# EFR32xG22_ESL-Node_Ref-Des_Sheet2.net
KiCad netlist of a schematic drawn in Altium Designer
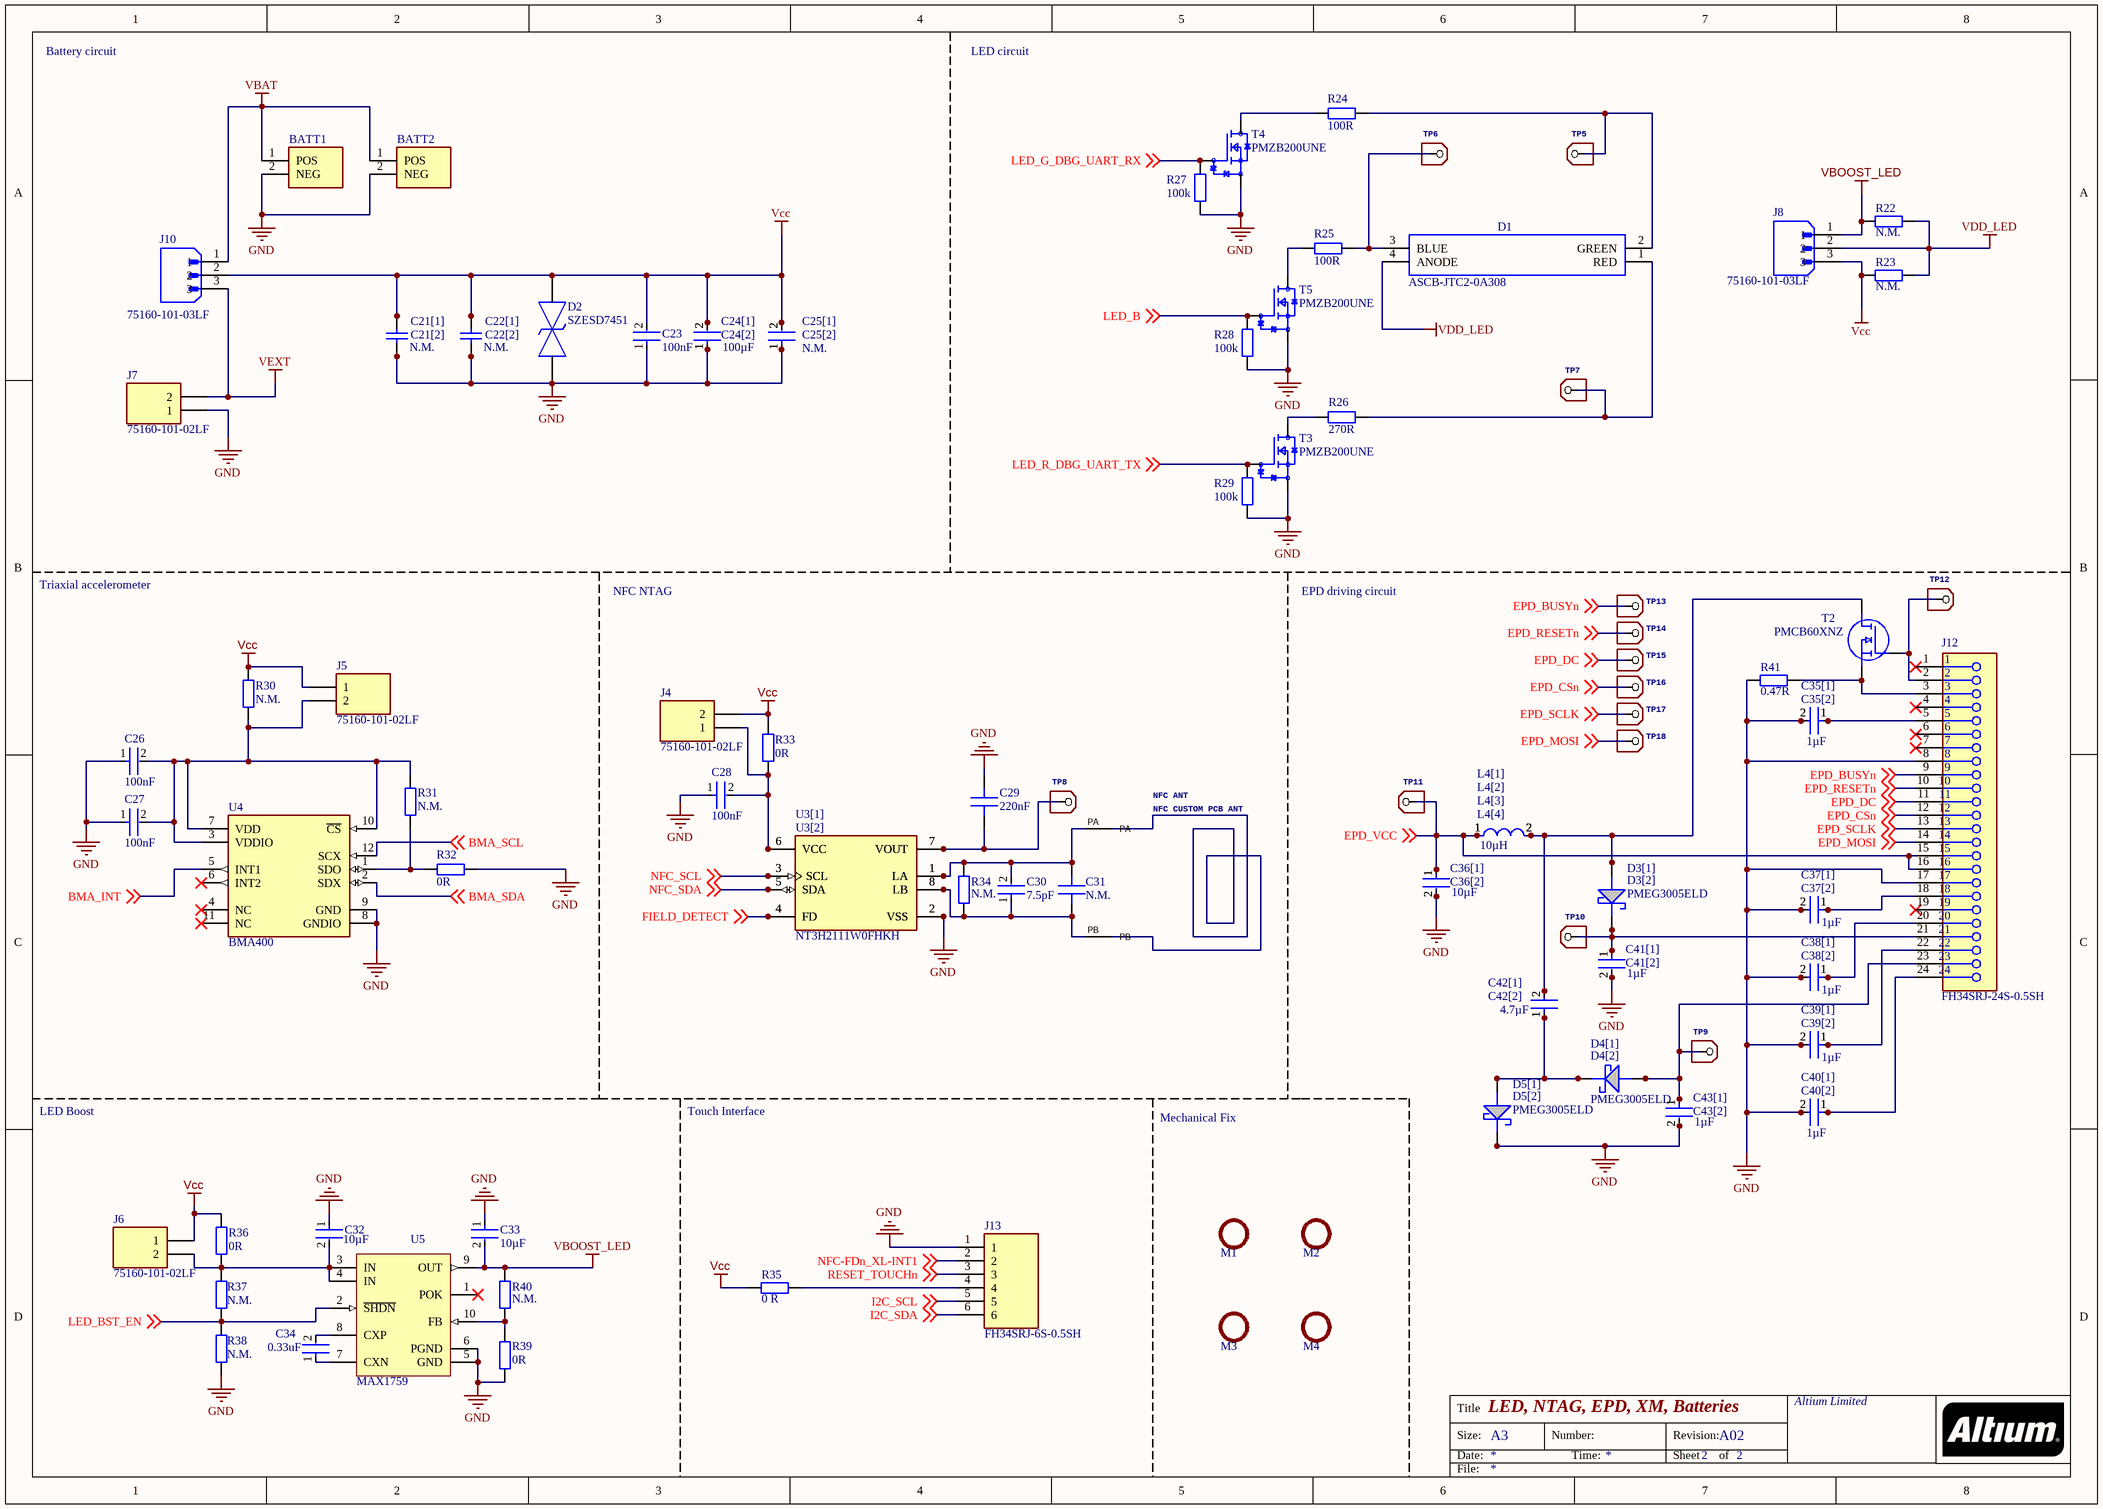
[diagram p0: EFR32xG22_ESL-Node_Ref-Des_Sheet2.SchDoc]

(export (version "E")
  (design (tool "Eeschema 10.0.6"))
  (components
    (comp (ref "BATT1")
      (value "1052TR")
      (footprint "Battery_holder_CR2450_SMT_1052")
      (description "Battery Holder _Open_ Coin, 24.5mm 1 Cell SMD _SMT_ Tab")
      (fields (field (name "MF") "Keystone Electronics"))
      (libsource (lib "EFR32xG22_ESL-Node_Ref-Des_1") (part "1052TR"))
    )
    (comp (ref "BATT2")
      (value "1052TR")
      (footprint "Battery_holder_CR2450_SMT_1052")
      (description "Battery Holder _Open_ Coin, 24.5mm 1 Cell SMD _SMT_ Tab")
      (fields (field (name "MF") "Keystone Electronics"))
      (libsource (lib "EFR32xG22_ESL-Node_Ref-Des_1") (part "1052TR"))
    )
    (comp (ref "C21[1]")
      (value "N.M.")
      (footprint "1206")
      (description "Chip Capacitor, 100 uF, +/- 20%, 6.3 V, -55 to 85 degC, 1206 (3216 Metric), RoHS, Tape and Reel")
      (fields (field (name "TOLERANCE") "20%") (field (name "PARTNUMBER") "GRM31CR60J107ME39L"))
      (libsource (lib "altium-import") (part "root_1_CAP-NP-2_"))
    )
    (comp (ref "C21[2]")
      (value "N.M.")
      (footprint "0805")
      (description "Chip Capacitor, 100 uF, +/- 20%, 6.3 V, -55 to 85 degC, 1206 (3216 Metric), RoHS, Tape and Reel")
      (fields (field (name "TOLERANCE") "20%") (field (name "PARTNUMBER") "GRM31CR60J107ME39L"))
      (libsource (lib "altium-import") (part "root_1_CAP-NP-2_"))
    )
    (comp (ref "C22[1]")
      (value "N.M.")
      (footprint "1206")
      (description "Chip Capacitor, 100 uF, +/- 20%, 6.3 V, -55 to 85 degC, 1206 (3216 Metric), RoHS, Tape and Reel")
      (fields (field (name "TOLERANCE") "20%") (field (name "PARTNUMBER") "GRM31CR60J107ME39L"))
      (libsource (lib "altium-import") (part "root_1_CAP-NP-2_"))
    )
    (comp (ref "C22[2]")
      (value "N.M.")
      (footprint "0805")
      (description "Chip Capacitor, 100 uF, +/- 20%, 6.3 V, -55 to 85 degC, 1206 (3216 Metric), RoHS, Tape and Reel")
      (fields (field (name "TOLERANCE") "20%") (field (name "PARTNUMBER") "GRM31CR60J107ME39L"))
      (libsource (lib "altium-import") (part "root_1_CAP-NP-2_"))
    )
    (comp (ref "C23")
      (value "100nF")
      (footprint "0402")
      (description "Ceramic Capacitor for Automotive 100nF ±10% 16VDC X7R 0402 Paper T/R")
      (fields (field (name "TOLERANCE") "10%"))
      (libsource (lib "altium-import") (part "root_2_02cd4be3c70576c341d710602a673aa_"))
    )
    (comp (ref "C24[1]")
      (value "100µF")
      (footprint "1206")
      (description "CAP CER 100UF 6.3V X5R 1206")
      (fields (field (name "VOLTAGE") "6.3V") (field (name "TOLERANCE") "20%"))
      (libsource (lib "altium-import") (part "root_2_b4654b650e69147ec39a6b967a45e02_"))
    )
    (comp (ref "C24[2]")
      (value "100µF")
      (footprint "0805")
      (description "CAP CER 100UF 6.3V X5R 1206")
      (fields (field (name "VOLTAGE") "6.3V") (field (name "TOLERANCE") "20%"))
      (libsource (lib "altium-import") (part "root_2_b4654b650e69147ec39a6b967a45e02_"))
    )
    (comp (ref "C25[1]")
      (value "N.M.")
      (footprint "1206")
      (description "CAP CER 100UF 6.3V X5R 1206")
      (fields (field (name "VOLTAGE") "6.3V") (field (name "TOLERANCE") "20%"))
      (libsource (lib "altium-import") (part "root_2_b4654b650e69147ec39a6b967a45e02_"))
    )
    (comp (ref "C25[2]")
      (value "100µF")
      (footprint "0805")
      (description "CAP CER 100UF 6.3V X5R 1206")
      (fields (field (name "VOLTAGE") "6.3V") (field (name "TOLERANCE") "20%"))
      (libsource (lib "altium-import") (part "root_2_b4654b650e69147ec39a6b967a45e02_"))
    )
    (comp (ref "C26")
      (value "100nF")
      (footprint "0402")
      (description "Ceramic Capacitor for Automotive 100nF ±10% 16VDC X7R 0402 Paper T/R")
      (fields (field (name "TOLERANCE") "10%"))
      (libsource (lib "altium-import") (part "root_1_02cd4be3c70576c341d710602a673aa_"))
    )
    (comp (ref "C27")
      (value "100nF")
      (footprint "0402")
      (description "Ceramic Capacitor for Automotive 100nF ±10% 16VDC X7R 0402 Paper T/R")
      (fields (field (name "TOLERANCE") "10%"))
      (libsource (lib "altium-import") (part "root_1_02cd4be3c70576c341d710602a673aa_"))
    )
    (comp (ref "C28")
      (value "100nF")
      (footprint "0201")
      (description "Chip Multilayer Ceramic Capacitors for General Purpose, 0201, 0.10uF, X5R, 15%, 10%, 10V")
      (fields (field (name "TOLERANCE") "10%") (field (name "VOLTAGE") "10V"))
      (libsource (lib "altium-import") (part "root_1_b4654b650e69147ec39a6b967a45e02_"))
    )
    (comp (ref "C29")
      (value "220nF")
      (footprint "0201")
      (description "CAP CER 1000PF 10V X7R 0201 10%")
      (fields (field (name "TOLERANCE") "10%"))
      (libsource (lib "altium-import") (part "root_3_Capacitor_"))
    )
    (comp (ref "C30")
      (value "7.5pF")
      (footprint "0201")
      (description "Chip Multilayer Ceramic Capacitors for General Purpose, 0201, 7.5pF, C0G, 30ppm/°C, 0.1pF, 50V")
      (libsource (lib "altium-import") (part "root_2_b4654b650e69147ec39a6b967a45e02_"))
    )
    (comp (ref "C31")
      (value "N.M.")
      (footprint "0201")
      (description "CAP CER 0201 C0G 1.2pF 50V 0.05pF")
      (fields (field (name "TOLERANCE") "0.05pF"))
      (libsource (lib "altium-import") (part "root_1_Capacitor_"))
    )
    (comp (ref "C32")
      (value "10µF")
      (footprint "0603")
      (description "Chip Multilayer Ceramic Capacitors for General Purpose, 0603, 10uF, X5R, 15%, 20%, 25V")
      (fields (field (name "TOLERANCE") "20%") (field (name "VOLTAGE") "25V"))
      (libsource (lib "altium-import") (part "root_0_11868f565c42a9108669ba33697ecf6_"))
    )
    (comp (ref "C33")
      (value "10µF")
      (footprint "0603")
      (description "Chip Multilayer Ceramic Capacitors for General Purpose, 0603, 10uF, X5R, 15%, 20%, 25V")
      (fields (field (name "TOLERANCE") "20%") (field (name "VOLTAGE") "25V"))
      (libsource (lib "altium-import") (part "root_0_11868f565c42a9108669ba33697ecf6_"))
    )
    (comp (ref "C34")
      (value "0.33uF")
      (footprint "0603")
      (description "Ceramic Capacitor for Automotive 330nF  ±10% 16VDC X7R 0603 Paper T/R")
      (fields (field (name "TOLERANCE") "10%"))
      (libsource (lib "altium-import") (part "root_2_02cd4be3c70576c341d710602a673aa_"))
    )
    (comp (ref "C35[1]")
      (value "1µF")
      (footprint "0603")
      (description "Ceramic Capacitor for Automotive 1uF  ±10% 25VDC X7R 0603 Paper T/R")
      (fields (field (name "TOLERANCE") "10%") (field (name "VOLTAGE") "25V"))
      (libsource (lib "altium-import") (part "root_3_02cd4be3c70576c341d710602a673aa_"))
    )
    (comp (ref "C35[2]")
      (value "1µF")
      (footprint "0402")
      (description "Ceramic Capacitor for Automotive 1uF  ±10% 25VDC X7R 0603 Paper T/R")
      (fields (field (name "TOLERANCE") "10%") (field (name "VOLTAGE") "25V"))
      (libsource (lib "altium-import") (part "root_3_02cd4be3c70576c341d710602a673aa_"))
    )
    (comp (ref "C36[1]")
      (value "10µF")
      (footprint "0603")
      (description "CAP CER 10UF 10V X5R 0603")
      (fields
        (field (name "OCTOPART") "https://octopart.com/grm188r61a106ke69d-murata-22851381")
        (field (name "MANUFACTURER PART NUMBER") "GRM188R61A106KE69D")
      )
      (libsource (lib "altium-import") (part "root_0_11868f565c42a9108669ba33697ecf6_"))
    )
    (comp (ref "C36[2]")
      (value "10µF")
      (footprint "0402")
      (description "CAP CER 10UF 10V X5R 0603")
      (fields
        (field (name "OCTOPART") "https://octopart.com/grm188r61a106ke69d-murata-22851381")
        (field (name "MANUFACTURER PART NUMBER") "GRM188R61A106KE69D")
      )
      (libsource (lib "altium-import") (part "root_0_11868f565c42a9108669ba33697ecf6_"))
    )
    (comp (ref "C37[1]")
      (value "1µF")
      (footprint "0603")
      (description "Ceramic Capacitor for Automotive 1uF  ±10% 25VDC X7R 0603 Paper T/R")
      (fields (field (name "TOLERANCE") "10%") (field (name "VOLTAGE") "25V"))
      (libsource (lib "altium-import") (part "root_3_02cd4be3c70576c341d710602a673aa_"))
    )
    (comp (ref "C37[2]")
      (value "1µF")
      (footprint "0402")
      (description "Ceramic Capacitor for Automotive 1uF  ±10% 25VDC X7R 0603 Paper T/R")
      (fields (field (name "TOLERANCE") "10%") (field (name "VOLTAGE") "25V"))
      (libsource (lib "altium-import") (part "root_3_02cd4be3c70576c341d710602a673aa_"))
    )
    (comp (ref "C38[1]")
      (value "1µF")
      (footprint "0603")
      (description "Ceramic Capacitor for Automotive 1uF  ±10% 25VDC X7R 0603 Paper T/R")
      (fields (field (name "TOLERANCE") "10%") (field (name "VOLTAGE") "25V"))
      (libsource (lib "altium-import") (part "root_3_02cd4be3c70576c341d710602a673aa_"))
    )
    (comp (ref "C38[2]")
      (value "1µF")
      (footprint "0402")
      (description "Ceramic Capacitor for Automotive 1uF  ±10% 25VDC X7R 0603 Paper T/R")
      (fields (field (name "TOLERANCE") "10%") (field (name "VOLTAGE") "25V"))
      (libsource (lib "altium-import") (part "root_3_02cd4be3c70576c341d710602a673aa_"))
    )
    (comp (ref "C39[1]")
      (value "1µF")
      (footprint "0603")
      (description "Ceramic Capacitor for Automotive 1uF  ±10% 25VDC X7R 0603 Paper T/R")
      (fields (field (name "TOLERANCE") "10%") (field (name "VOLTAGE") "25V"))
      (libsource (lib "altium-import") (part "root_3_02cd4be3c70576c341d710602a673aa_"))
    )
    (comp (ref "C39[2]")
      (value "1µF")
      (footprint "0402")
      (description "Ceramic Capacitor for Automotive 1uF  ±10% 25VDC X7R 0603 Paper T/R")
      (fields (field (name "TOLERANCE") "10%") (field (name "VOLTAGE") "25V"))
      (libsource (lib "altium-import") (part "root_3_02cd4be3c70576c341d710602a673aa_"))
    )
    (comp (ref "C40[1]")
      (value "1µF")
      (footprint "0603")
      (description "Ceramic Capacitor for Automotive 1uF  ±10% 25VDC X7R 0603 Paper T/R")
      (fields (field (name "TOLERANCE") "10%") (field (name "VOLTAGE") "25V"))
      (libsource (lib "altium-import") (part "root_3_02cd4be3c70576c341d710602a673aa_"))
    )
    (comp (ref "C40[2]")
      (value "1µF")
      (footprint "0402")
      (description "Ceramic Capacitor for Automotive 1uF  ±10% 25VDC X7R 0603 Paper T/R")
      (fields (field (name "TOLERANCE") "10%") (field (name "VOLTAGE") "25V"))
      (libsource (lib "altium-import") (part "root_3_02cd4be3c70576c341d710602a673aa_"))
    )
    (comp (ref "C41[1]")
      (value "1µF")
      (footprint "0603")
      (description "CAP CER 10UF 10V X5R 0603")
      (fields
        (field (name "OCTOPART") "https://octopart.com/grm188r61a106ke69d-murata-22851381")
        (field (name "MANUFACTURER PART NUMBER") "GRM188R61A106KE69D")
      )
      (libsource (lib "altium-import") (part "root_0_11868f565c42a9108669ba33697ecf6_"))
    )
    (comp (ref "C41[2]")
      (value "1µF")
      (footprint "0402")
      (description "CAP CER 10UF 10V X5R 0603")
      (fields
        (field (name "OCTOPART") "https://octopart.com/grm188r61a106ke69d-murata-22851381")
        (field (name "MANUFACTURER PART NUMBER") "GRM188R61A106KE69D")
      )
      (libsource (lib "altium-import") (part "root_0_11868f565c42a9108669ba33697ecf6_"))
    )
    (comp (ref "C42[1]")
      (value "4.7µF")
      (footprint "0603")
      (description "CAP CER 10UF 10V X5R 0603")
      (fields
        (field (name "OCTOPART") "https://octopart.com/grm188r61a106ke69d-murata-22851381")
        (field (name "MANUFACTURER PART NUMBER") "GRM188R61A106KE69D")
      )
      (libsource (lib "altium-import") (part "root_2_11868f565c42a9108669ba33697ecf6_"))
    )
    (comp (ref "C42[2]")
      (value "4.7µF")
      (footprint "0402")
      (description "CAP CER 10UF 10V X5R 0603")
      (fields
        (field (name "OCTOPART") "https://octopart.com/grm188r61a106ke69d-murata-22851381")
        (field (name "MANUFACTURER PART NUMBER") "GRM188R61A106KE69D")
      )
      (libsource (lib "altium-import") (part "root_2_11868f565c42a9108669ba33697ecf6_"))
    )
    (comp (ref "C43[1]")
      (value "1µF")
      (footprint "0603")
      (description "CAP CER 10UF 10V X5R 0603")
      (fields
        (field (name "OCTOPART") "https://octopart.com/grm188r61a106ke69d-murata-22851381")
        (field (name "MANUFACTURER PART NUMBER") "GRM188R61A106KE69D")
      )
      (libsource (lib "altium-import") (part "root_0_11868f565c42a9108669ba33697ecf6_"))
    )
    (comp (ref "C43[2]")
      (value "1µF")
      (footprint "0402")
      (description "CAP CER 10UF 10V X5R 0603")
      (fields
        (field (name "OCTOPART") "https://octopart.com/grm188r61a106ke69d-murata-22851381")
        (field (name "MANUFACTURER PART NUMBER") "GRM188R61A106KE69D")
      )
      (libsource (lib "altium-import") (part "root_0_11868f565c42a9108669ba33697ecf6_"))
    )
    (comp (ref "D1")
      (value "ASCB-JTC2-0A308")
      (footprint "LED_RGB_PLCC-4")
      (description "Standard LEDs - SMD 1615 Tricolor PLCC-4 LED")
      (fields (field (name "MOUSER PART NUMBER") "630-ASCB-JTC2-0A308"))
      (libsource (lib "ASCBJTC20A308") (part "ASCB-JTC2-0A308"))
    )
    (comp (ref "D2")
      (value "SZESD7451")
      (footprint "SOD882_NXP")
      (description "ESD Suppressors / TVS Diodes BI-DIRECTIONAL 5V ESD PR")
      (fields
        (field (name "MANUFACTURER_PART_NUMBER") "ESD7551N2T5G")
        (field (name "MOUSER PART NUMBER") "863-ESD7551N2T5G")
      )
      (libsource (lib "EFR32xG22_ESL-Node_Ref-Des_1") (part "ESD7551N2T5G"))
    )
    (comp (ref "D3[1]")
      (value "PMEG3005ELD")
      (footprint "SOD-323")
      (description "Schottky Diodes & Rectifiers Schottky Diode")
      (fields
        (field (name "MANUFACTURER_PART_NUMBER") "PMEG3005ELD,315")
        (field (name "MOUSER PART NUMBER") "771-PMEG3005ELD315")
      )
      (libsource (lib "EFR32xG22_ESL-Node_Ref-Des_1") (part "PMEG3005ELD_315"))
    )
    (comp (ref "D3[2]")
      (value "PMEG3005ELD")
      (footprint "SOD882_FIXED")
      (description "Schottky Diodes & Rectifiers Schottky Diode")
      (fields
        (field (name "MANUFACTURER_PART_NUMBER") "PMEG3005ELD,315")
        (field (name "MOUSER PART NUMBER") "771-PMEG3005ELD315")
      )
      (libsource (lib "EFR32xG22_ESL-Node_Ref-Des_1") (part "PMEG3005ELD_315"))
    )
    (comp (ref "D4[1]")
      (value "PMEG3005ELD")
      (footprint "SOD-323")
      (description "Schottky Diodes & Rectifiers Schottky Diode")
      (fields
        (field (name "MANUFACTURER_PART_NUMBER") "PMEG3005ELD,315")
        (field (name "MOUSER PART NUMBER") "771-PMEG3005ELD315")
      )
      (libsource (lib "EFR32xG22_ESL-Node_Ref-Des_1") (part "PMEG3005ELD_315"))
    )
    (comp (ref "D4[2]")
      (value "PMEG3005ELD")
      (footprint "SOD882_FIXED")
      (description "Schottky Diodes & Rectifiers Schottky Diode")
      (fields
        (field (name "MANUFACTURER_PART_NUMBER") "PMEG3005ELD,315")
        (field (name "MOUSER PART NUMBER") "771-PMEG3005ELD315")
      )
      (libsource (lib "EFR32xG22_ESL-Node_Ref-Des_1") (part "PMEG3005ELD_315"))
    )
    (comp (ref "D5[1]")
      (value "PMEG3005ELD")
      (footprint "SOD-323")
      (description "Schottky Diodes & Rectifiers Schottky Diode")
      (fields
        (field (name "MANUFACTURER_PART_NUMBER") "PMEG3005ELD,315")
        (field (name "MOUSER PART NUMBER") "771-PMEG3005ELD315")
      )
      (libsource (lib "EFR32xG22_ESL-Node_Ref-Des_1") (part "PMEG3005ELD_315"))
    )
    (comp (ref "D5[2]")
      (value "PMEG3005ELD")
      (footprint "SOD882_FIXED")
      (description "Schottky Diodes & Rectifiers Schottky Diode")
      (fields
        (field (name "MANUFACTURER_PART_NUMBER") "PMEG3005ELD,315")
        (field (name "MOUSER PART NUMBER") "771-PMEG3005ELD315")
      )
      (libsource (lib "EFR32xG22_ESL-Node_Ref-Des_1") (part "PMEG3005ELD_315"))
    )
    (comp (ref "J4")
      (value "75160-101-02LF")
      (footprint "Jumper_HDR_2.54mm")
      (fields (field (name "MP") "HTSW10228FS") (field (name "MF") "Samtec"))
      (libsource (lib "EFR32xG22_ESL-Node_Ref-Des_1") (part "HTSW-102-28-F-S"))
    )
    (comp (ref "J5")
      (value "75160-101-02LF")
      (footprint "Jumper_HDR_2.54mm")
      (fields (field (name "MP") "HTSW10228FS") (field (name "MF") "Samtec"))
      (libsource (lib "") (part "HTSW-102-28-F-S_2"))
    )
    (comp (ref "J6")
      (value "75160-101-02LF")
      (footprint "Jumper_HDR_2.54mm")
      (fields (field (name "MP") "HTSW10228FS") (field (name "MF") "Samtec"))
      (libsource (lib "") (part "HTSW-102-28-F-S_1"))
    )
    (comp (ref "J7")
      (value "75160-101-02LF")
      (footprint "Jumper_HDR_2.54mm")
      (fields (field (name "MP") "HTSW10228FS") (field (name "MF") "Samtec"))
      (libsource (lib "EFR32xG22_ESL-Node_Ref-Des_1") (part "HTSW-102-28-F-S"))
    )
    (comp (ref "J8")
      (value "75160-101-03LF")
      (footprint "Jumper_HDR_2.54mm_3p")
      (fields (field (name "MF") "Amphenol ICC (FCI)"))
      (libsource (lib "75160-101-03LF") (part "75160-101-03LF"))
    )
    (comp (ref "J10")
      (value "75160-101-03LF")
      (footprint "Jumper_HDR_2.54mm_3p")
      (fields (field (name "MF") "Amphenol ICC (FCI)"))
      (libsource (lib "75160-101-03LF") (part "75160-101-03LF"))
    )
    (comp (ref "J12")
      (value "FH34SRJ-24S-0.5SH")
      (footprint "FPC_CONNECTOR_24_0.5MM_PITCH_BOTTOM_CONTACT_ACES_1.3MM_50530")
      (description "CONN FPC/FFC 24POS .5MM")
      (libsource (lib "EFR32xG22_ESL-Node_Ref-Des_1") (part "CMP-11609-000022-1"))
    )
    (comp (ref "J13")
      (value "FH34SRJ-6S-0.5SH")
      (footprint "FH34SRJ-6S-0.5SH")
      (fields (field (name "MP") "FH34SRJ-6S-0.5SH(50)"))
      (libsource (lib "EFR32xG22_ESL-Node_Ref-Des_1") (part "FH34SRJ-6S-0.5SH(50)"))
    )
    (comp (ref "L4[1]")
      (value "10µH")
      (footprint "0805")
      (description "SMD Inductors 10uH ±10% 0.52A 0.65Ω 0806")
      (fields (field (name "TOLERANCE") "10%"))
      (libsource (lib "altium-import") (part "root_0_725321dda6339637d4d059423bc1c3c_"))
    )
    (comp (ref "L4[2]")
      (value "10µH")
      (footprint "0806")
      (description "SMD Inductors 10uH ±10% 0.52A 0.65Ω 0806")
      (fields (field (name "TOLERANCE") "10%"))
      (libsource (lib "altium-import") (part "root_0_725321dda6339637d4d059423bc1c3c_"))
    )
    (comp (ref "L4[3]")
      (value "10µH")
      (footprint "2520")
      (description "SMD Inductors 10uH ±10% 0.52A 0.65Ω 0806")
      (fields (field (name "TOLERANCE") "10%"))
      (libsource (lib "altium-import") (part "root_0_725321dda6339637d4d059423bc1c3c_"))
    )
    (comp (ref "L4[4]")
      (value "10µH")
      (footprint "WE-MAPI-3015")
      (description "SMD Inductors 10uH ±10% 0.52A 0.65Ω 0806")
      (fields (field (name "TOLERANCE") "10%"))
      (libsource (lib "altium-import") (part "root_0_725321dda6339637d4d059423bc1c3c_"))
    )
    (comp (ref "M1")
      (value "HOLE_2.2_NPL")
      (footprint "HOLE_2.2_NPL")
      (libsource (lib "EFR32xG22_ESL-Node_Ref-Des_Sheet2") (part "HOLE_2.2_NPL"))
    )
    (comp (ref "M2")
      (value "HOLE_2.2_NPL")
      (footprint "HOLE_2.2_NPL")
      (libsource (lib "EFR32xG22_ESL-Node_Ref-Des_Sheet2") (part "HOLE_2.2_NPL"))
    )
    (comp (ref "M3")
      (value "HOLE_2.2_NPL")
      (footprint "HOLE_2.2_NPL")
      (libsource (lib "EFR32xG22_ESL-Node_Ref-Des_Sheet2") (part "HOLE_2.2_NPL"))
    )
    (comp (ref "M4")
      (value "HOLE_2.2_NPL")
      (footprint "HOLE_2.2_NPL")
      (libsource (lib "EFR32xG22_ESL-Node_Ref-Des_Sheet2") (part "HOLE_2.2_NPL"))
    )
    (comp (ref "NFC ANT")
      (value "NFC CUSTOM PCB ANT")
      (footprint "NFC_27X14.3_7W_WIDTH0.25MM_SPACE0.2MM_1.5UH_V1_0_NOVIASTOP")
      (description "Custom NFC Printed Antenna")
      (libsource (lib "EFR32xG22_ESL-Node_Ref-Des_1") (part "NFC_ANTENNA_custom"))
    )
    (comp (ref "R22")
      (value "N.M.")
      (footprint "0603")
      (fields (field (name "MANUFACTURER") "Vishay Dale") (field (name "PART NUMBER") "CRCW06030000Z0EC"))
      (libsource (lib "altium-import") (part "root_2_RES_"))
    )
    (comp (ref "R23")
      (value "N.M.")
      (footprint "0603")
      (fields (field (name "MANUFACTURER") "Vishay Dale") (field (name "PART NUMBER") "CRCW06030000Z0EC"))
      (libsource (lib "altium-import") (part "root_2_RES_"))
    )
    (comp (ref "R24")
      (value "100R")
      (footprint "0201")
      (description "RES 0201 100R 1/20W 1% 200ppm")
      (fields (field (name "TOLERANCE") "1%"))
      (libsource (lib "altium-import") (part "root_0_Resistor_"))
    )
    (comp (ref "R25")
      (value "100R")
      (footprint "0201")
      (description "RES 0201 100R 1/20W 1% 200ppm")
      (fields (field (name "TOLERANCE") "1%"))
      (libsource (lib "altium-import") (part "root_0_Resistor_"))
    )
    (comp (ref "R26")
      (value "270R")
      (footprint "0201")
      (description "240R 0.05W 5% 0201 (0603 Metric)  SMD")
      (fields (field (name "TOLERANCE") "5 %") (field (name "POWER") "0.05 W"))
      (libsource (lib "altium-import") (part "root_0_RES_"))
    )
    (comp (ref "R27")
      (value "100k")
      (footprint "0201")
      (description "100K 0.05W 1% 0201 (0603 Metric)  SMD")
      (fields (field (name "POWER") "0.05 W") (field (name "TOLERANCE") "1 %"))
      (libsource (lib "altium-import") (part "root_1_RES_"))
    )
    (comp (ref "R28")
      (value "100k")
      (footprint "0201")
      (description "100K 0.05W 1% 0201 (0603 Metric)  SMD")
      (fields (field (name "POWER") "0.05 W") (field (name "TOLERANCE") "1 %"))
      (libsource (lib "altium-import") (part "root_1_RES_"))
    )
    (comp (ref "R29")
      (value "100k")
      (footprint "0201")
      (description "100K 0.05W 1% 0201 (0603 Metric)  SMD")
      (fields (field (name "POWER") "0.05 W") (field (name "TOLERANCE") "1 %"))
      (libsource (lib "altium-import") (part "root_1_RES_"))
    )
    (comp (ref "R30")
      (value "N.M.")
      (footprint "0603")
      (fields (field (name "MANUFACTURER") "Vishay Dale") (field (name "PART NUMBER") "CRCW06030000Z0EC"))
      (libsource (lib "altium-import") (part "root_1_RES_"))
    )
    (comp (ref "R31")
      (value "N.M.")
      (footprint "0201")
      (description "RES 0201 0R")
      (fields (field (name "TOLERANCE") "0%"))
      (libsource (lib "altium-import") (part "root_3_Resistor_"))
    )
    (comp (ref "R32")
      (value "0R")
      (footprint "0201")
      (description "RES 0201 0R")
      (fields (field (name "TOLERANCE") "0%"))
      (libsource (lib "altium-import") (part "root_2_Resistor_"))
    )
    (comp (ref "R33")
      (value "0R")
      (footprint "0603")
      (fields (field (name "MANUFACTURER") "Vishay Dale") (field (name "PART NUMBER") "CRCW06030000Z0EC"))
      (libsource (lib "altium-import") (part "root_1_RES_"))
    )
    (comp (ref "R34")
      (value "N.M.")
      (footprint "0201")
      (description "RES 0201 0R")
      (fields (field (name "TOLERANCE") "0%"))
      (libsource (lib "altium-import") (part "root_1_Resistor_"))
    )
    (comp (ref "R35")
      (value "0 R")
      (footprint "0603")
      (fields (field (name "MANUFACTURER") "Vishay Dale") (field (name "PART NUMBER") "CRCW06030000Z0EC"))
      (libsource (lib "altium-import") (part "root_2_RES_"))
    )
    (comp (ref "R36")
      (value "0R")
      (footprint "0603")
      (fields (field (name "MANUFACTURER") "Vishay Dale") (field (name "PART NUMBER") "CRCW06030000Z0EC"))
      (libsource (lib "altium-import") (part "root_1_RES_"))
    )
    (comp (ref "R37")
      (value "N.M.")
      (footprint "0603")
      (fields (field (name "MANUFACTURER") "Vishay Dale") (field (name "PART NUMBER") "CRCW06030000Z0EC"))
      (libsource (lib "altium-import") (part "root_1_RES_"))
    )
    (comp (ref "R38")
      (value "N.M.")
      (footprint "0603")
      (fields (field (name "MANUFACTURER") "Vishay Dale") (field (name "PART NUMBER") "CRCW06030000Z0EC"))
      (libsource (lib "altium-import") (part "root_1_RES_"))
    )
    (comp (ref "R39")
      (value "0R")
      (footprint "0201")
      (description "RES 0201 0R")
      (fields (field (name "TOLERANCE") "0%"))
      (libsource (lib "altium-import") (part "root_1_Resistor_"))
    )
    (comp (ref "R40")
      (value "N.M.")
      (footprint "0201")
      (description "RES 0201 0R")
      (fields (field (name "TOLERANCE") "0%"))
      (libsource (lib "altium-import") (part "root_1_Resistor_"))
    )
    (comp (ref "R41")
      (value "0.47R")
      (footprint "0402")
      (fields (field (name "PART NUMBER") "RL0510S-R47-F") (field (name "MANUFACTURER") "Susumu"))
      (libsource (lib "altium-import") (part "root_2_RES_"))
    )
    (comp (ref "T2")
      (value "PMCB60XNZ")
      (footprint "SOT8026")
      (description "MOSFET PMCB60XN - 30 V, N-channel Trench MOSFET")
      (fields (field (name "MOUSER PART NUMBER") "771-PMCB60XNZ"))
      (libsource (lib "EFR32xG22_ESL-Node_Ref-Des_1") (part "PMCB60XNZ"))
    )
    (comp (ref "T3")
      (value "PMZB200UNE")
      (footprint "SOT883_B_FIXED")
      (description "N-Channel 20V 1.2A (Ta) 350mW (Ta), 5.43W (Tc) Surface Mount DFN1006B-3")
      (fields (field (name "MP") "PMZB290UNE") (field (name "MF") "NXP Semiconductors"))
      (libsource (lib "EFR32xG22_ESL-Node_Ref-Des_1") (part "PMZB290UNE"))
    )
    (comp (ref "T4")
      (value "PMZB200UNE")
      (footprint "SOT883_B_FIXED")
      (description "N-Channel 20V 1.2A (Ta) 350mW (Ta), 5.43W (Tc) Surface Mount DFN1006B-3")
      (fields (field (name "MP") "PMZB290UNE") (field (name "MF") "NXP Semiconductors"))
      (libsource (lib "EFR32xG22_ESL-Node_Ref-Des_1") (part "PMZB290UNE"))
    )
    (comp (ref "T5")
      (value "PMZB200UNE")
      (footprint "SOT883_B_FIXED")
      (description "N-Channel 20V 1.2A (Ta) 350mW (Ta), 5.43W (Tc) Surface Mount DFN1006B-3")
      (fields (field (name "MP") "PMZB290UNE") (field (name "MF") "NXP Semiconductors"))
      (libsource (lib "EFR32xG22_ESL-Node_Ref-Des_1") (part "PMZB290UNE"))
    )
    (comp (ref "TP5")
      (value "TPSMDR1")
      (footprint "TP_RPAD1")
      (description "Testpoint")
      (libsource (lib "EFR32xG22_ESL-Node_Ref-Des") (part "TPSMDR1"))
    )
    (comp (ref "TP6")
      (value "TPSMDR1")
      (footprint "TP_RPAD1")
      (description "Testpoint")
      (libsource (lib "EFR32xG22_ESL-Node_Ref-Des") (part "TPSMDR1"))
    )
    (comp (ref "TP7")
      (value "TPSMDR1")
      (footprint "TP_RPAD1")
      (description "Testpoint")
      (libsource (lib "EFR32xG22_ESL-Node_Ref-Des") (part "TPSMDR1"))
    )
    (comp (ref "TP8")
      (value "TPSMDR1")
      (footprint "TP_RPAD1")
      (description "Testpoint")
      (libsource (lib "EFR32xG22_ESL-Node_Ref-Des") (part "TPSMDR1"))
    )
    (comp (ref "TP9")
      (value "TPSMDR1")
      (footprint "TP_RPAD1")
      (description "Testpoint")
      (libsource (lib "EFR32xG22_ESL-Node_Ref-Des") (part "TPSMDR1"))
    )
    (comp (ref "TP10")
      (value "TPSMDR1")
      (footprint "TP_RPAD1")
      (description "Testpoint")
      (libsource (lib "EFR32xG22_ESL-Node_Ref-Des") (part "TPSMDR1"))
    )
    (comp (ref "TP11")
      (value "TPSMDR1")
      (footprint "TP_RPAD1")
      (description "Testpoint")
      (libsource (lib "EFR32xG22_ESL-Node_Ref-Des") (part "TPSMDR1"))
    )
    (comp (ref "TP12")
      (value "TPSMDR1")
      (footprint "TP_RPAD1")
      (description "Testpoint")
      (libsource (lib "EFR32xG22_ESL-Node_Ref-Des") (part "TPSMDR1"))
    )
    (comp (ref "TP13")
      (value "TPSMDR1")
      (footprint "TP_RPAD1")
      (description "Testpoint")
      (libsource (lib "EFR32xG22_ESL-Node_Ref-Des") (part "TPSMDR1"))
    )
    (comp (ref "TP14")
      (value "TPSMDR1")
      (footprint "TP_RPAD1")
      (description "Testpoint")
      (libsource (lib "EFR32xG22_ESL-Node_Ref-Des") (part "TPSMDR1"))
    )
    (comp (ref "TP15")
      (value "TPSMDR1")
      (footprint "TP_RPAD1")
      (description "Testpoint")
      (libsource (lib "EFR32xG22_ESL-Node_Ref-Des") (part "TPSMDR1"))
    )
    (comp (ref "TP16")
      (value "TPSMDR1")
      (footprint "TP_RPAD1")
      (description "Testpoint")
      (libsource (lib "EFR32xG22_ESL-Node_Ref-Des") (part "TPSMDR1"))
    )
    (comp (ref "TP17")
      (value "TPSMDR1")
      (footprint "TP_RPAD1")
      (description "Testpoint")
      (libsource (lib "EFR32xG22_ESL-Node_Ref-Des") (part "TPSMDR1"))
    )
    (comp (ref "TP18")
      (value "TPSMDR1")
      (footprint "TP_RPAD1")
      (description "Testpoint")
      (libsource (lib "EFR32xG22_ESL-Node_Ref-Des") (part "TPSMDR1"))
    )
    (comp (ref "U3[1]")
      (value "NT3H2111W0FHKH")
      (footprint "SO8_SOIC127P600X175-8N")
      (description "IC RFID TRANSP 13.56MHZ 8XQFN")
      (fields
        (field (name "MANUFACTURER") "NXP")
        (field (name "OCTOPART") "https://octopart.com/nt3h2111w0fhkh-nxp+semiconductors-71112033")
      )
      (libsource (lib "altium-import") (part "root_0_39eb1c674dcfd8f95a63d21f9f9692a_"))
    )
    (comp (ref "U3[2]")
      (value "NT3H2111W0FHKH")
      (footprint "XQFN-8")
      (description "IC RFID TRANSP 13.56MHZ 8XQFN")
      (fields
        (field (name "MANUFACTURER") "NXP")
        (field (name "OCTOPART") "https://octopart.com/nt3h2111w0fhkh-nxp+semiconductors-71112033")
      )
      (libsource (lib "altium-import") (part "root_0_39eb1c674dcfd8f95a63d21f9f9692a_"))
    )
    (comp (ref "U4")
      (value "BMA400")
      (footprint "BMA400")
      (description "ACCELEROMETER 2-16G 12LGA")
      (fields
        (field (name "MANUFACTURER") "Bosch Sensortec")
        (field (name "OCTOPART") "https://octopart.com/bma400-bosch+sensortec-106101410")
      )
      (libsource (lib "altium-import") (part "root_0_752ad95c2281fff0f5c1d2aa84f0ac6_"))
    )
    (comp (ref "U5")
      (value "MAX1759")
      (footprint "UMAX10")
      (description "Buck/Boost Regulating Charge Pump, open-drain POK, 10-Pin uMAX, -40°C to +85°C, Pb-Free")
      (libsource (lib "altium-import") (part "root_0_MAX-MAX1759-IL10_"))
    )
  )
  (nets
    (net (code "1") (name "BMA_INT") (class "Default")
      (node (ref "U4") (pin "5") (pinfunction "INT1_5") (pintype "output"))
    )
    (net (code "2") (name "BMA_SCL") (class "Default")
      (node (ref "U4") (pin "12") (pinfunction "SCX_12") (pintype "input"))
    )
    (net (code "3") (name "BMA_SDA") (class "Default")
      (node (ref "U4") (pin "2") (pinfunction "SDX_2") (pintype "bidirectional"))
    )
    (net (code "4") (name "EPD_BUSYn") (class "Default")
      (node (ref "J12") (pin "9") (pinfunction "9_9") (pintype "passive"))
      (node (ref "TP13") (pin "P$1") (pinfunction "1_P$1") (pintype "passive"))
    )
    (net (code "5") (name "EPD_CSn") (class "Default")
      (node (ref "J12") (pin "12") (pinfunction "12_12") (pintype "passive"))
      (node (ref "TP16") (pin "P$1") (pinfunction "1_P$1") (pintype "passive"))
    )
    (net (code "6") (name "EPD_DC") (class "Default")
      (node (ref "J12") (pin "11") (pinfunction "11_11") (pintype "passive"))
      (node (ref "TP15") (pin "P$1") (pinfunction "1_P$1") (pintype "passive"))
    )
    (net (code "7") (name "EPD_MOSI") (class "Default")
      (node (ref "J12") (pin "14") (pinfunction "14_14") (pintype "passive"))
      (node (ref "TP18") (pin "P$1") (pinfunction "1_P$1") (pintype "passive"))
    )
    (net (code "8") (name "EPD_RESETn") (class "Default")
      (node (ref "J12") (pin "10") (pinfunction "10_10") (pintype "passive"))
      (node (ref "TP14") (pin "P$1") (pinfunction "1_P$1") (pintype "passive"))
    )
    (net (code "9") (name "EPD_SCLK") (class "Default")
      (node (ref "J12") (pin "13") (pinfunction "13_13") (pintype "passive"))
      (node (ref "TP17") (pin "P$1") (pinfunction "1_P$1") (pintype "passive"))
    )
    (net (code "10") (name "EPD_VCC") (class "Default")
      (node (ref "C36[1]") (pin "1") (pinfunction "1_1") (pintype "passive"))
      (node (ref "C36[2]") (pin "1") (pinfunction "1_1") (pintype "passive"))
      (node (ref "J12") (pin "15") (pinfunction "15_15") (pintype "passive"))
      (node (ref "J12") (pin "16") (pinfunction "16_16") (pintype "passive"))
      (node (ref "L4[1]") (pin "1") (pinfunction "1_1") (pintype "passive"))
      (node (ref "L4[2]") (pin "1") (pinfunction "1_1") (pintype "passive"))
      (node (ref "L4[3]") (pin "1") (pinfunction "1_1") (pintype "passive"))
      (node (ref "L4[4]") (pin "1") (pinfunction "1_1") (pintype "passive"))
      (node (ref "TP11") (pin "P$1") (pinfunction "1_P$1") (pintype "passive"))
    )
    (net (code "11") (name "FIELD_DETECT") (class "Default")
      (node (ref "U3[1]") (pin "4") (pinfunction "FD_4") (pintype "passive"))
      (node (ref "U3[2]") (pin "4") (pinfunction "FD_4") (pintype "passive"))
    )
    (net (code "12") (name "GND") (class "Default")
      (node (ref "BATT1") (pin "2") (pinfunction "NEG_2") (pintype "passive"))
      (node (ref "BATT2") (pin "2") (pinfunction "NEG_2") (pintype "passive"))
      (node (ref "C21[1]") (pin "1") (pinfunction "1_1") (pintype "passive"))
      (node (ref "C21[2]") (pin "1") (pinfunction "1_1") (pintype "passive"))
      (node (ref "C22[1]") (pin "1") (pinfunction "1_1") (pintype "passive"))
      (node (ref "C22[2]") (pin "1") (pinfunction "1_1") (pintype "passive"))
      (node (ref "C23") (pin "1") (pinfunction "1_1") (pintype "passive"))
      (node (ref "C24[1]") (pin "1") (pinfunction "1_1") (pintype "passive"))
      (node (ref "C24[2]") (pin "1") (pinfunction "1_1") (pintype "passive"))
      (node (ref "C25[1]") (pin "1") (pinfunction "1_1") (pintype "passive"))
      (node (ref "C25[2]") (pin "1") (pinfunction "1_1") (pintype "passive"))
      (node (ref "C26") (pin "1") (pinfunction "1_1") (pintype "passive"))
      (node (ref "C27") (pin "1") (pinfunction "1_1") (pintype "passive"))
      (node (ref "C28") (pin "1") (pinfunction "1_1") (pintype "passive"))
      (node (ref "C29") (pin "1") (pinfunction "1_1") (pintype "passive"))
      (node (ref "C32") (pin "1") (pinfunction "1_1") (pintype "passive"))
      (node (ref "C33") (pin "1") (pinfunction "1_1") (pintype "passive"))
      (node (ref "C35[1]") (pin "2") (pinfunction "2_2") (pintype "passive"))
      (node (ref "C35[2]") (pin "2") (pinfunction "2_2") (pintype "passive"))
      (node (ref "C36[1]") (pin "2") (pinfunction "2_2") (pintype "passive"))
      (node (ref "C36[2]") (pin "2") (pinfunction "2_2") (pintype "passive"))
      (node (ref "C37[1]") (pin "2") (pinfunction "2_2") (pintype "passive"))
      (node (ref "C37[2]") (pin "2") (pinfunction "2_2") (pintype "passive"))
      (node (ref "C38[1]") (pin "2") (pinfunction "2_2") (pintype "passive"))
      (node (ref "C38[2]") (pin "2") (pinfunction "2_2") (pintype "passive"))
      (node (ref "C39[1]") (pin "2") (pinfunction "2_2") (pintype "passive"))
      (node (ref "C39[2]") (pin "2") (pinfunction "2_2") (pintype "passive"))
      (node (ref "C40[1]") (pin "2") (pinfunction "2_2") (pintype "passive"))
      (node (ref "C40[2]") (pin "2") (pinfunction "2_2") (pintype "passive"))
      (node (ref "C41[1]") (pin "2") (pinfunction "2_2") (pintype "passive"))
      (node (ref "C41[2]") (pin "2") (pinfunction "2_2") (pintype "passive"))
      (node (ref "C43[1]") (pin "2") (pinfunction "2_2") (pintype "passive"))
      (node (ref "C43[2]") (pin "2") (pinfunction "2_2") (pintype "passive"))
      (node (ref "D2") (pin "A") (pinfunction "2_A") (pintype "passive"))
      (node (ref "D5[1]") (pin "C") (pinfunction "C_C") (pintype "passive"))
      (node (ref "D5[2]") (pin "C") (pinfunction "C_C") (pintype "passive"))
      (node (ref "J12") (pin "17") (pinfunction "17_17") (pintype "passive"))
      (node (ref "J12") (pin "8") (pinfunction "8_8") (pintype "passive"))
      (node (ref "J13") (pin "1") (pinfunction "1_1") (pintype "passive"))
      (node (ref "J7") (pin "1") (pinfunction "1_1") (pintype "passive"))
      (node (ref "R27") (pin "1") (pinfunction "1_1") (pintype "passive"))
      (node (ref "R28") (pin "1") (pinfunction "1_1") (pintype "passive"))
      (node (ref "R29") (pin "1") (pinfunction "1_1") (pintype "passive"))
      (node (ref "R32") (pin "1") (pinfunction "1_1") (pintype "passive"))
      (node (ref "R38") (pin "1") (pinfunction "1_1") (pintype "passive"))
      (node (ref "R39") (pin "1") (pinfunction "1_1") (pintype "passive"))
      (node (ref "R41") (pin "2") (pinfunction "2_2") (pintype "passive"))
      (node (ref "T3") (pin "S") (pinfunction "S_S") (pintype "passive"))
      (node (ref "T4") (pin "S") (pinfunction "S_S") (pintype "passive"))
      (node (ref "T5") (pin "S") (pinfunction "S_S") (pintype "passive"))
      (node (ref "U3[1]") (pin "2") (pinfunction "VSS_2") (pintype "power_in"))
      (node (ref "U3[2]") (pin "2") (pinfunction "VSS_2") (pintype "power_in"))
      (node (ref "U4") (pin "8") (pinfunction "GNDIO_8") (pintype "power_in"))
      (node (ref "U4") (pin "9") (pinfunction "GND_9") (pintype "power_in"))
      (node (ref "U5") (pin "5") (pinfunction "GND_5") (pintype "power_in"))
      (node (ref "U5") (pin "6") (pinfunction "PGND_6") (pintype "power_in"))
    )
    (net (code "13") (name "I2C_SCL") (class "Default")
      (node (ref "J13") (pin "5") (pinfunction "5_5") (pintype "passive"))
    )
    (net (code "14") (name "I2C_SDA") (class "Default")
      (node (ref "J13") (pin "6") (pinfunction "6_6") (pintype "passive"))
    )
    (net (code "15") (name "LED_B") (class "Default")
      (node (ref "R28") (pin "2") (pinfunction "2_2") (pintype "passive"))
      (node (ref "T5") (pin "G") (pinfunction "G_G") (pintype "passive"))
    )
    (net (code "16") (name "LED_BST_EN") (class "Default")
      (node (ref "R37") (pin "1") (pinfunction "1_1") (pintype "passive"))
      (node (ref "R38") (pin "2") (pinfunction "2_2") (pintype "passive"))
      (node (ref "U5") (pin "2") (pinfunction "~{SHDN}_2") (pintype "input"))
    )
    (net (code "17") (name "LED_G_DBG_UART_RX") (class "Default")
      (node (ref "R27") (pin "2") (pinfunction "2_2") (pintype "passive"))
      (node (ref "T4") (pin "G") (pinfunction "G_G") (pintype "passive"))
    )
    (net (code "18") (name "LED_R_DBG_UART_TX") (class "Default")
      (node (ref "R29") (pin "2") (pinfunction "2_2") (pintype "passive"))
      (node (ref "T3") (pin "G") (pinfunction "G_G") (pintype "passive"))
    )
    (net (code "19") (name "NFC-FDn_XL-INT1") (class "Default")
      (node (ref "J13") (pin "2") (pinfunction "2_2") (pintype "passive"))
    )
    (net (code "20") (name "NFC_SCL") (class "Default")
      (node (ref "U3[1]") (pin "3") (pinfunction "SCL_3") (pintype "input"))
      (node (ref "U3[2]") (pin "3") (pinfunction "SCL_3") (pintype "input"))
    )
    (net (code "21") (name "NFC_SDA") (class "Default")
      (node (ref "U3[1]") (pin "5") (pinfunction "SDA_5") (pintype "bidirectional"))
      (node (ref "U3[2]") (pin "5") (pinfunction "SDA_5") (pintype "bidirectional"))
    )
    (net (code "22") (name "Net-(C32-Pad2)") (class "Default")
      (node (ref "C32") (pin "2") (pinfunction "2_2") (pintype "passive"))
      (node (ref "J6") (pin "2") (pinfunction "2_2") (pintype "passive"))
      (node (ref "R36") (pin "1") (pinfunction "1_1") (pintype "passive"))
      (node (ref "R37") (pin "2") (pinfunction "2_2") (pintype "passive"))
      (node (ref "U5") (pin "3") (pinfunction "IN_3") (pintype "power_in"))
      (node (ref "U5") (pin "4") (pinfunction "IN_4") (pintype "power_in"))
    )
    (net (code "23") (name "Net-(C35[1]-Pad1)") (class "Default")
      (node (ref "C35[1]") (pin "1") (pinfunction "1_1") (pintype "passive"))
      (node (ref "C35[2]") (pin "1") (pinfunction "1_1") (pintype "passive"))
      (node (ref "J12") (pin "5") (pinfunction "5_5") (pintype "passive"))
    )
    (net (code "24") (name "Net-(C37[1]-Pad1)") (class "Default")
      (node (ref "C37[1]") (pin "1") (pinfunction "1_1") (pintype "passive"))
      (node (ref "C37[2]") (pin "1") (pinfunction "1_1") (pintype "passive"))
      (node (ref "J12") (pin "18") (pinfunction "18_18") (pintype "passive"))
    )
    (net (code "25") (name "Net-(C38[1]-Pad1)") (class "Default")
      (node (ref "C38[1]") (pin "1") (pinfunction "1_1") (pintype "passive"))
      (node (ref "C38[2]") (pin "1") (pinfunction "1_1") (pintype "passive"))
      (node (ref "J12") (pin "20") (pinfunction "20_20") (pintype "passive"))
    )
    (net (code "26") (name "Net-(C39[1]-Pad1)") (class "Default")
      (node (ref "C39[1]") (pin "1") (pinfunction "1_1") (pintype "passive"))
      (node (ref "C39[2]") (pin "1") (pinfunction "1_1") (pintype "passive"))
      (node (ref "J12") (pin "22") (pinfunction "22_22") (pintype "passive"))
    )
    (net (code "27") (name "Net-(C40[1]-Pad1)") (class "Default")
      (node (ref "C40[1]") (pin "1") (pinfunction "1_1") (pintype "passive"))
      (node (ref "C40[2]") (pin "1") (pinfunction "1_1") (pintype "passive"))
      (node (ref "J12") (pin "24") (pinfunction "24_24") (pintype "passive"))
    )
    (net (code "28") (name "Net-(C42[1]-Pad1)") (class "Default")
      (node (ref "C42[1]") (pin "1") (pinfunction "1_1") (pintype "passive"))
      (node (ref "C42[2]") (pin "1") (pinfunction "1_1") (pintype "passive"))
      (node (ref "D4[1]") (pin "C") (pinfunction "C_C") (pintype "passive"))
      (node (ref "D4[2]") (pin "C") (pinfunction "C_C") (pintype "passive"))
      (node (ref "D5[1]") (pin "A") (pinfunction "A_A") (pintype "passive"))
      (node (ref "D5[2]") (pin "A") (pinfunction "A_A") (pintype "passive"))
    )
    (net (code "29") (name "Net-(C42[1]-Pad2)") (class "Default")
      (node (ref "C42[1]") (pin "2") (pinfunction "2_2") (pintype "passive"))
      (node (ref "C42[2]") (pin "2") (pinfunction "2_2") (pintype "passive"))
      (node (ref "D3[1]") (pin "A") (pinfunction "A_A") (pintype "passive"))
      (node (ref "D3[2]") (pin "A") (pinfunction "A_A") (pintype "passive"))
      (node (ref "L4[1]") (pin "2") (pinfunction "2_2") (pintype "passive"))
      (node (ref "L4[2]") (pin "2") (pinfunction "2_2") (pintype "passive"))
      (node (ref "L4[3]") (pin "2") (pinfunction "2_2") (pintype "passive"))
      (node (ref "L4[4]") (pin "2") (pinfunction "2_2") (pintype "passive"))
      (node (ref "T2") (pin "D") (pinfunction "D_D") (pintype "passive"))
    )
    (net (code "30") (name "Net-(D1-BLUE)") (class "Default")
      (node (ref "D1") (pin "3") (pinfunction "BLUE_3") (pintype "passive"))
      (node (ref "R25") (pin "2") (pinfunction "2_2") (pintype "passive"))
      (node (ref "TP6") (pin "P$1") (pinfunction "1_P$1") (pintype "passive"))
    )
    (net (code "31") (name "Net-(D1-GREEN)") (class "Default")
      (node (ref "D1") (pin "2") (pinfunction "GREEN_2") (pintype "passive"))
      (node (ref "R24") (pin "2") (pinfunction "2_2") (pintype "passive"))
      (node (ref "TP5") (pin "P$1") (pinfunction "1_P$1") (pintype "passive"))
    )
    (net (code "32") (name "Net-(D1-RED)") (class "Default")
      (node (ref "D1") (pin "1") (pinfunction "RED_1") (pintype "passive"))
      (node (ref "R26") (pin "2") (pinfunction "2_2") (pintype "passive"))
      (node (ref "TP7") (pin "P$1") (pinfunction "1_P$1") (pintype "passive"))
    )
    (net (code "33") (name "Net-(J12-Pad3)") (class "Default")
      (node (ref "J12") (pin "3") (pinfunction "3_3") (pintype "passive"))
      (node (ref "R41") (pin "1") (pinfunction "1_1") (pintype "passive"))
      (node (ref "T2") (pin "S") (pinfunction "S_S") (pintype "passive"))
    )
    (net (code "34") (name "Net-(J13-Pad4)") (class "Default")
      (node (ref "J13") (pin "4") (pinfunction "4_4") (pintype "passive"))
      (node (ref "R35") (pin "1") (pinfunction "1_1") (pintype "passive"))
    )
    (net (code "35") (name "Net-(R24-Pad1)") (class "Default")
      (node (ref "R24") (pin "1") (pinfunction "1_1") (pintype "passive"))
      (node (ref "T4") (pin "D") (pinfunction "D_D") (pintype "passive"))
    )
    (net (code "36") (name "Net-(R25-Pad1)") (class "Default")
      (node (ref "R25") (pin "1") (pinfunction "1_1") (pintype "passive"))
      (node (ref "T5") (pin "D") (pinfunction "D_D") (pintype "passive"))
    )
    (net (code "37") (name "Net-(R26-Pad1)") (class "Default")
      (node (ref "R26") (pin "1") (pinfunction "1_1") (pintype "passive"))
      (node (ref "T3") (pin "D") (pinfunction "D_D") (pintype "passive"))
    )
    (net (code "38") (name "Net-(TP8-1)") (class "Default")
      (node (ref "C29") (pin "2") (pinfunction "2_2") (pintype "passive"))
      (node (ref "TP8") (pin "P$1") (pinfunction "1_P$1") (pintype "passive"))
      (node (ref "U3[1]") (pin "7") (pinfunction "VOUT_7") (pintype "power_in"))
      (node (ref "U3[2]") (pin "7") (pinfunction "VOUT_7") (pintype "power_in"))
    )
    (net (code "39") (name "Net-(TP9-1)") (class "Default")
      (node (ref "C43[1]") (pin "1") (pinfunction "1_1") (pintype "passive"))
      (node (ref "C43[2]") (pin "1") (pinfunction "1_1") (pintype "passive"))
      (node (ref "D4[1]") (pin "A") (pinfunction "A_A") (pintype "passive"))
      (node (ref "D4[2]") (pin "A") (pinfunction "A_A") (pintype "passive"))
      (node (ref "J12") (pin "23") (pinfunction "23_23") (pintype "passive"))
      (node (ref "TP9") (pin "P$1") (pinfunction "1_P$1") (pintype "passive"))
    )
    (net (code "40") (name "Net-(TP10-1)") (class "Default")
      (node (ref "C41[1]") (pin "1") (pinfunction "1_1") (pintype "passive"))
      (node (ref "C41[2]") (pin "1") (pinfunction "1_1") (pintype "passive"))
      (node (ref "D3[1]") (pin "C") (pinfunction "C_C") (pintype "passive"))
      (node (ref "D3[2]") (pin "C") (pinfunction "C_C") (pintype "passive"))
      (node (ref "J12") (pin "21") (pinfunction "21_21") (pintype "passive"))
      (node (ref "TP10") (pin "P$1") (pinfunction "1_P$1") (pintype "passive"))
    )
    (net (code "41") (name "Net-(TP12-1)") (class "Default")
      (node (ref "J12") (pin "2") (pinfunction "2_2") (pintype "passive"))
      (node (ref "T2") (pin "G") (pinfunction "G_G") (pintype "passive"))
      (node (ref "TP12") (pin "P$1") (pinfunction "1_P$1") (pintype "passive"))
    )
    (net (code "42") (name "Net-(U3[1]-LA)") (class "Default")
      (node (ref "C30") (pin "2") (pinfunction "2_2") (pintype "passive"))
      (node (ref "C31") (pin "2") (pinfunction "2_2") (pintype "passive"))
      (node (ref "NFC ANT") (pin "PA") (pinfunction "PA_PA") (pintype "passive"))
      (node (ref "R34") (pin "2") (pinfunction "2_2") (pintype "passive"))
      (node (ref "U3[1]") (pin "1") (pinfunction "LA_1") (pintype "passive"))
      (node (ref "U3[2]") (pin "1") (pinfunction "LA_1") (pintype "passive"))
    )
    (net (code "43") (name "Net-(U3[1]-LB)") (class "Default")
      (node (ref "C30") (pin "1") (pinfunction "1_1") (pintype "passive"))
      (node (ref "C31") (pin "1") (pinfunction "1_1") (pintype "passive"))
      (node (ref "NFC ANT") (pin "PB") (pinfunction "PB_PB") (pintype "passive"))
      (node (ref "R34") (pin "1") (pinfunction "1_1") (pintype "passive"))
      (node (ref "U3[1]") (pin "8") (pinfunction "LB_8") (pintype "passive"))
      (node (ref "U3[2]") (pin "8") (pinfunction "LB_8") (pintype "passive"))
    )
    (net (code "44") (name "Net-(U3[1]-VCC)") (class "Default")
      (node (ref "C28") (pin "2") (pinfunction "2_2") (pintype "passive"))
      (node (ref "J4") (pin "1") (pinfunction "1_1") (pintype "passive"))
      (node (ref "R33") (pin "1") (pinfunction "1_1") (pintype "passive"))
      (node (ref "U3[1]") (pin "6") (pinfunction "VCC_6") (pintype "power_in"))
      (node (ref "U3[2]") (pin "6") (pinfunction "VCC_6") (pintype "power_in"))
    )
    (net (code "45") (name "Net-(U4-SDO)") (class "Default")
      (node (ref "R31") (pin "2") (pinfunction "2_2") (pintype "passive"))
      (node (ref "R32") (pin "2") (pinfunction "2_2") (pintype "passive"))
      (node (ref "U4") (pin "1") (pinfunction "SDO_1") (pintype "bidirectional"))
    )
    (net (code "46") (name "Net-(U4-VDD)") (class "Default")
      (node (ref "C26") (pin "2") (pinfunction "2_2") (pintype "passive"))
      (node (ref "C27") (pin "2") (pinfunction "2_2") (pintype "passive"))
      (node (ref "J5") (pin "2") (pinfunction "2_2") (pintype "passive"))
      (node (ref "R30") (pin "1") (pinfunction "1_1") (pintype "passive"))
      (node (ref "R31") (pin "1") (pinfunction "1_1") (pintype "passive"))
      (node (ref "U4") (pin "10") (pinfunction "~{CS}_10") (pintype "input"))
      (node (ref "U4") (pin "3") (pinfunction "VDDIO_3") (pintype "power_in"))
      (node (ref "U4") (pin "7") (pinfunction "VDD_7") (pintype "power_in"))
    )
    (net (code "47") (name "Net-(U5-CXN)") (class "Default")
      (node (ref "C34") (pin "1") (pinfunction "1_1") (pintype "passive"))
      (node (ref "U5") (pin "7") (pinfunction "CXN_7") (pintype "passive"))
    )
    (net (code "48") (name "Net-(U5-CXP)") (class "Default")
      (node (ref "C34") (pin "2") (pinfunction "2_2") (pintype "passive"))
      (node (ref "U5") (pin "8") (pinfunction "CXP_8") (pintype "passive"))
    )
    (net (code "49") (name "Net-(U5-FB)") (class "Default")
      (node (ref "R39") (pin "2") (pinfunction "2_2") (pintype "passive"))
      (node (ref "R40") (pin "1") (pinfunction "1_1") (pintype "passive"))
      (node (ref "U5") (pin "10") (pinfunction "FB_10") (pintype "input"))
    )
    (net (code "50") (name "RESET_TOUCHn") (class "Default")
      (node (ref "J13") (pin "3") (pinfunction "3_3") (pintype "passive"))
    )
    (net (code "51") (name "VBAT") (class "Default")
      (node (ref "BATT1") (pin "1") (pinfunction "POS_1") (pintype "passive"))
      (node (ref "BATT2") (pin "1") (pinfunction "POS_1") (pintype "passive"))
      (node (ref "J10") (pin "1") (pinfunction "1_1") (pintype "passive"))
    )
    (net (code "52") (name "VBOOST_LED") (class "Default")
      (node (ref "C33") (pin "2") (pinfunction "2_2") (pintype "passive"))
      (node (ref "J8") (pin "1") (pinfunction "1_1") (pintype "passive"))
      (node (ref "R22") (pin "2") (pinfunction "2_2") (pintype "passive"))
      (node (ref "R40") (pin "2") (pinfunction "2_2") (pintype "passive"))
      (node (ref "U5") (pin "9") (pinfunction "OUT_9") (pintype "output"))
    )
    (net (code "53") (name "VDD_LED") (class "Default")
      (node (ref "D1") (pin "4") (pinfunction "ANODE_4") (pintype "passive"))
      (node (ref "J8") (pin "2") (pinfunction "2_2") (pintype "passive"))
      (node (ref "R22") (pin "1") (pinfunction "1_1") (pintype "passive"))
      (node (ref "R23") (pin "1") (pinfunction "1_1") (pintype "passive"))
    )
    (net (code "54") (name "VEXT") (class "Default")
      (node (ref "J10") (pin "3") (pinfunction "3_3") (pintype "passive"))
      (node (ref "J7") (pin "2") (pinfunction "2_2") (pintype "passive"))
    )
    (net (code "55") (name "Vcc") (class "Default")
      (node (ref "C21[1]") (pin "2") (pinfunction "2_2") (pintype "passive"))
      (node (ref "C21[2]") (pin "2") (pinfunction "2_2") (pintype "passive"))
      (node (ref "C22[1]") (pin "2") (pinfunction "2_2") (pintype "passive"))
      (node (ref "C22[2]") (pin "2") (pinfunction "2_2") (pintype "passive"))
      (node (ref "C23") (pin "2") (pinfunction "2_2") (pintype "passive"))
      (node (ref "C24[1]") (pin "2") (pinfunction "2_2") (pintype "passive"))
      (node (ref "C24[2]") (pin "2") (pinfunction "2_2") (pintype "passive"))
      (node (ref "C25[1]") (pin "2") (pinfunction "2_2") (pintype "passive"))
      (node (ref "C25[2]") (pin "2") (pinfunction "2_2") (pintype "passive"))
      (node (ref "D2") (pin "C") (pinfunction "1_C") (pintype "passive"))
      (node (ref "J10") (pin "2") (pinfunction "2_2") (pintype "passive"))
      (node (ref "J4") (pin "2") (pinfunction "2_2") (pintype "passive"))
      (node (ref "J5") (pin "1") (pinfunction "1_1") (pintype "passive"))
      (node (ref "J6") (pin "1") (pinfunction "1_1") (pintype "passive"))
      (node (ref "J8") (pin "3") (pinfunction "3_3") (pintype "passive"))
      (node (ref "R23") (pin "2") (pinfunction "2_2") (pintype "passive"))
      (node (ref "R30") (pin "2") (pinfunction "2_2") (pintype "passive"))
      (node (ref "R33") (pin "2") (pinfunction "2_2") (pintype "passive"))
      (node (ref "R35") (pin "2") (pinfunction "2_2") (pintype "passive"))
      (node (ref "R36") (pin "2") (pinfunction "2_2") (pintype "passive"))
    )
    (net (code "56") (name "unconnected-(J12-Pad1)") (class "Default")
      (node (ref "J12") (pin "1") (pinfunction "1_1") (pintype "passive+no_connect"))
    )
    (net (code "57") (name "unconnected-(J12-Pad4)") (class "Default")
      (node (ref "J12") (pin "4") (pinfunction "4_4") (pintype "passive+no_connect"))
    )
    (net (code "58") (name "unconnected-(J12-Pad6)") (class "Default")
      (node (ref "J12") (pin "6") (pinfunction "6_6") (pintype "passive+no_connect"))
    )
    (net (code "59") (name "unconnected-(J12-Pad7)") (class "Default")
      (node (ref "J12") (pin "7") (pinfunction "7_7") (pintype "passive+no_connect"))
    )
    (net (code "60") (name "unconnected-(J12-Pad19)") (class "Default")
      (node (ref "J12") (pin "19") (pinfunction "19_19") (pintype "passive+no_connect"))
    )
    (net (code "61") (name "unconnected-(M1-Pad0)") (class "Default")
      (node (ref "M1") (pin "0") (pinfunction "0_0") (pintype "passive"))
    )
    (net (code "62") (name "unconnected-(M2-Pad0)") (class "Default")
      (node (ref "M2") (pin "0") (pinfunction "0_0") (pintype "passive"))
    )
    (net (code "63") (name "unconnected-(M3-Pad0)") (class "Default")
      (node (ref "M3") (pin "0") (pinfunction "0_0") (pintype "passive"))
    )
    (net (code "64") (name "unconnected-(M4-Pad0)") (class "Default")
      (node (ref "M4") (pin "0") (pinfunction "0_0") (pintype "passive"))
    )
    (net (code "65") (name "unconnected-(U4-INT2-Pad6)") (class "Default")
      (node (ref "U4") (pin "6") (pinfunction "INT2_6") (pintype "output+no_connect"))
    )
    (net (code "66") (name "unconnected-(U4-NC-Pad4)") (class "Default")
      (node (ref "U4") (pin "4") (pinfunction "NC_4") (pintype "passive+no_connect"))
    )
    (net (code "67") (name "unconnected-(U4-NC-Pad11)") (class "Default")
      (node (ref "U4") (pin "11") (pinfunction "NC_11") (pintype "passive+no_connect"))
    )
    (net (code "68") (name "unconnected-(U5-POK-Pad1)") (class "Default")
      (node (ref "U5") (pin "1") (pinfunction "POK_1") (pintype "open_collector+no_connect"))
    )
  )
)
